# Graphic_LCD_Backpack.net
KiCad netlist of a schematic drawn in EAGLE
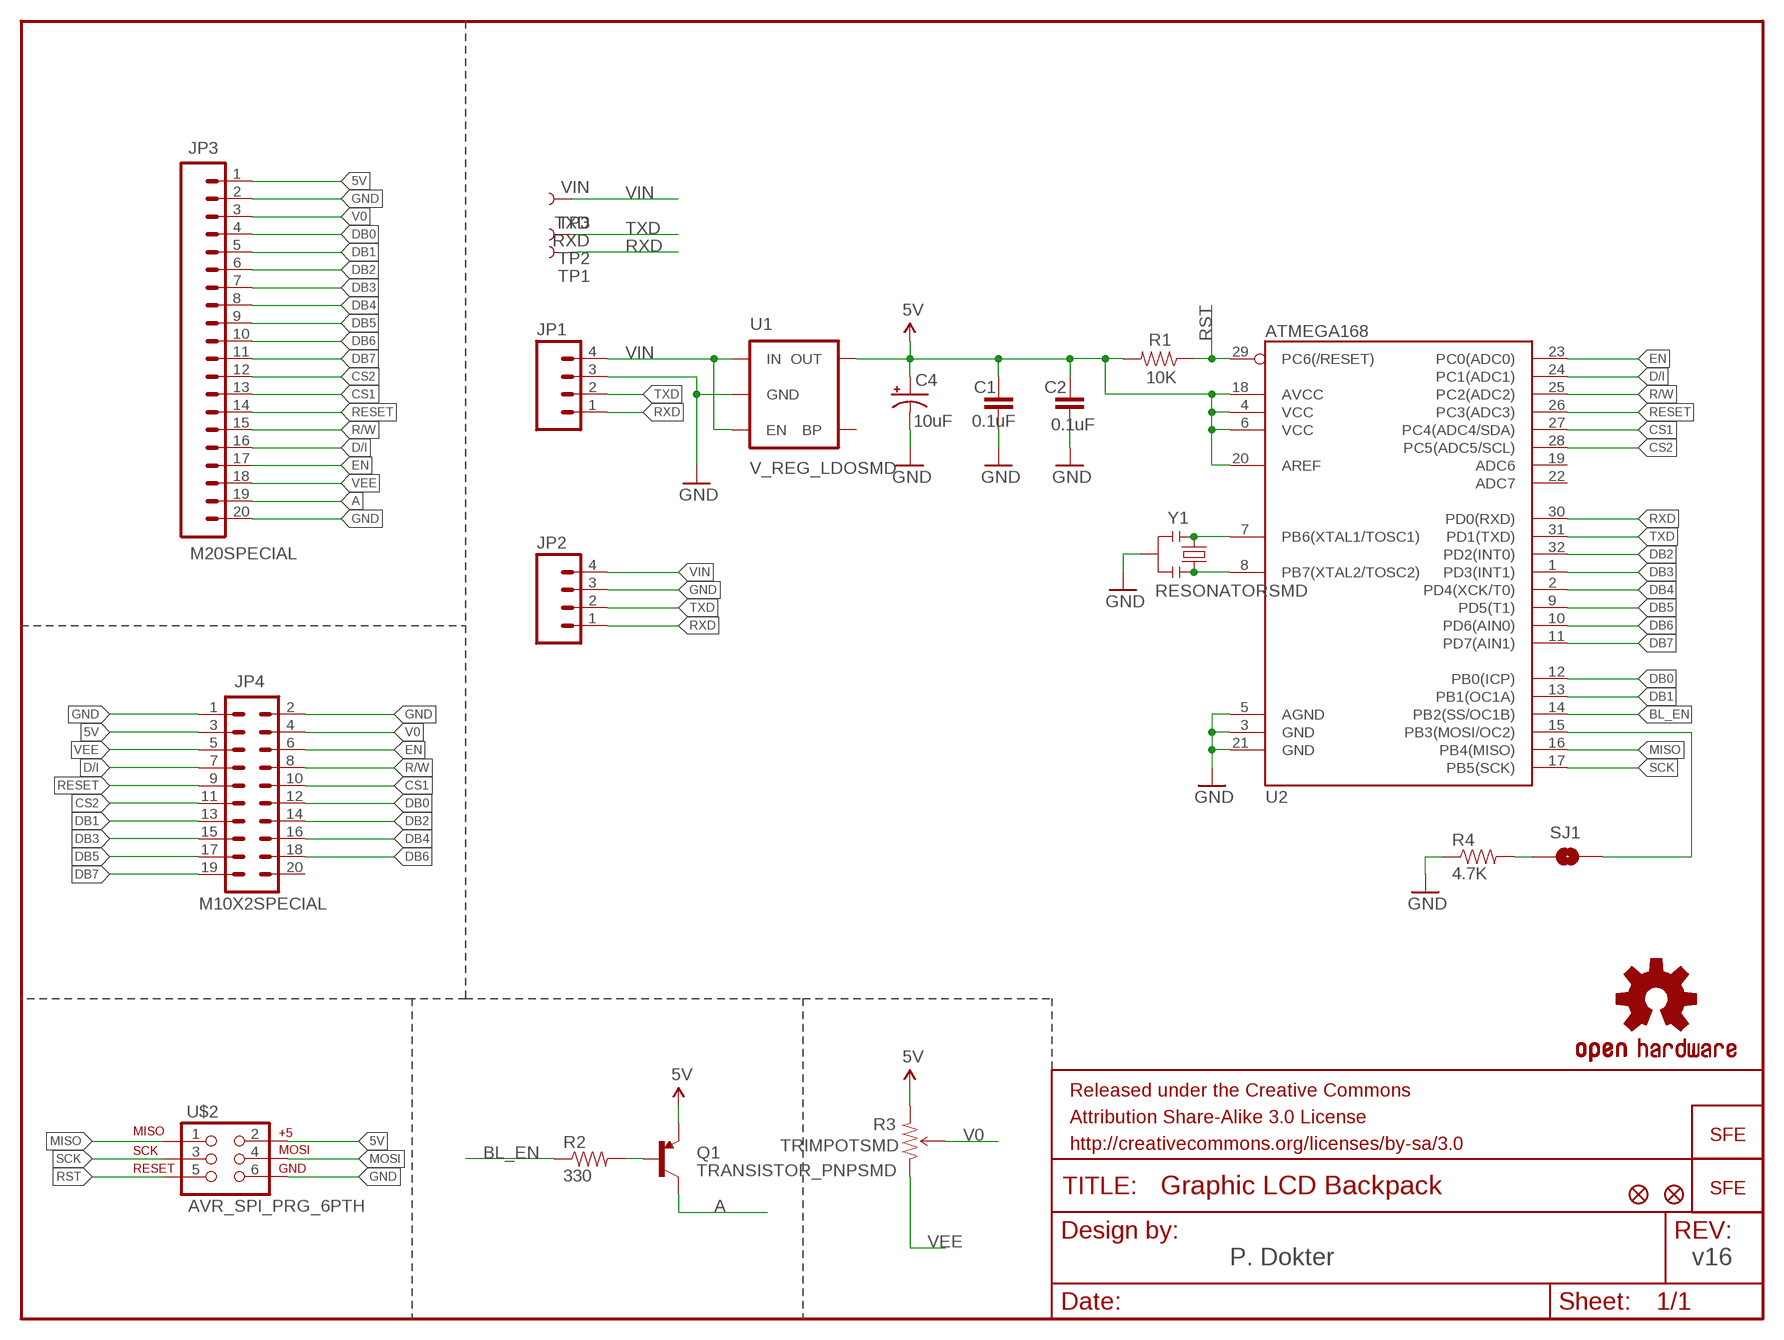
[diagram p0: schematic, sheet 1]

(export (version "E")
  (design (tool "Eeschema 10.0.6"))
  (components
    (comp (ref "C1")
      (value "0.1uF")
      (footprint "eagle-import:0603-CAP")
      (libsource (lib "eagle-import") (part "CAP0603-CAP"))
    )
    (comp (ref "C2")
      (value "0.1uF")
      (footprint "eagle-import:0603-CAP")
      (libsource (lib "eagle-import") (part "CAP0603-CAP"))
    )
    (comp (ref "C4")
      (value "10uF")
      (footprint "eagle-import:EIA3216")
      (libsource (lib "eagle-import") (part "CAP_POL1206"))
    )
    (comp (ref "FRAME1")
      (value "FRAME-LETTER")
      (footprint "eagle-import:CREATIVE_COMMONS")
      (libsource (lib "eagle-import") (part "FRAME-LETTER"))
    )
    (comp (ref "JP1")
      (value "M04SMD")
      (footprint "eagle-import:1X04-SMD")
      (libsource (lib "eagle-import") (part "M04SMD"))
    )
    (comp (ref "JP2")
      (value "M04PTH")
      (footprint "eagle-import:1X04")
      (libsource (lib "eagle-import") (part "M04PTH"))
    )
    (comp (ref "JP3")
      (value "M20SPECIAL")
      (footprint "eagle-import:1X20_LOCK_SPECIAL")
      (libsource (lib "eagle-import") (part "M20SPECIAL"))
    )
    (comp (ref "JP4")
      (value "M10X2SPECIAL")
      (footprint "eagle-import:2X10_LOCK_SPECIAL")
      (libsource (lib "eagle-import") (part "M10X2SPECIAL"))
    )
    (comp (ref "LOGO1")
      (value "OSHW-LOGOL")
      (footprint "eagle-import:OSHW-LOGO-L")
      (libsource (lib "eagle-import") (part "OSHW-LOGOL"))
    )
    (comp (ref "LOGO2")
      (value "LOGO-SFENEW")
      (footprint "eagle-import:SFE-NEW-WEBLOGO")
      (libsource (lib "eagle-import") (part "SparkFun-Aesthetics_LOGO-SFENEW"))
    )
    (comp (ref "LOGO3")
      (value "OSHW-LOGOS")
      (footprint "eagle-import:OSHW-LOGO-S")
      (libsource (lib "eagle-import") (part "OSHW-LOGOS"))
    )
    (comp (ref "Q1")
      (value "TRANSISTOR_PNPSMD")
      (footprint "eagle-import:SOT23-3")
      (libsource (lib "eagle-import") (part "TRANSISTOR_PNPSMD"))
    )
    (comp (ref "R1")
      (value "10K")
      (footprint "eagle-import:0603-RES")
      (libsource (lib "eagle-import") (part "RESISTOR0603-RES"))
    )
    (comp (ref "R2")
      (value "330")
      (footprint "eagle-import:0603-RES")
      (libsource (lib "eagle-import") (part "RESISTOR0603-RES"))
    )
    (comp (ref "R3")
      (value "TRIMPOTSMD")
      (footprint "eagle-import:TRIMPOT-3MM")
      (libsource (lib "eagle-import") (part "TRIMPOTSMD"))
    )
    (comp (ref "R4")
      (value "4.7K")
      (footprint "eagle-import:0603-RES")
      (libsource (lib "eagle-import") (part "RESISTOR0603-RES"))
    )
    (comp (ref "SJ1")
      (value "SOLDERJUMPERNC2")
      (footprint "eagle-import:SJ_2S-NOTRACE")
      (libsource (lib "eagle-import") (part "SOLDERJUMPERNC2"))
    )
    (comp (ref "TP1")
      (value "RXD")
      (footprint "eagle-import:PAD.03X.05")
      (libsource (lib "eagle-import") (part "TEST-POINT3X5"))
    )
    (comp (ref "TP2")
      (value "TXD")
      (footprint "eagle-import:PAD.03X.05")
      (libsource (lib "eagle-import") (part "TEST-POINT3X5"))
    )
    (comp (ref "TP3")
      (value "VIN")
      (footprint "eagle-import:PAD.03X.05")
      (libsource (lib "eagle-import") (part "TEST-POINT3X5"))
    )
    (comp (ref "U$2")
      (value "AVR_SPI_PRG_6PTH")
      (footprint "eagle-import:2X3")
      (libsource (lib "eagle-import") (part "AVR_SPI_PRG_6PTH"))
    )
    (comp (ref "U$8")
      (value "LOGO-SFENEW")
      (footprint "eagle-import:SFE-NEW-WEBLOGO")
      (libsource (lib "eagle-import") (part "LOGO-SFENEW"))
    )
    (comp (ref "U$9")
      (value "FIDUCIAL1X2")
      (footprint "eagle-import:FIDUCIAL-1X2")
      (libsource (lib "eagle-import") (part "FIDUCIAL1X2"))
    )
    (comp (ref "U$10")
      (value "FIDUCIAL1X2")
      (footprint "eagle-import:FIDUCIAL-1X2")
      (libsource (lib "eagle-import") (part "FIDUCIAL1X2"))
    )
    (comp (ref "U1")
      (value "V_REG_LDOSMD")
      (footprint "eagle-import:SOT23-5")
      (libsource (lib "eagle-import") (part "V_REG_LDOSMD"))
    )
    (comp (ref "U2")
      (value "ATMEGA168")
      (footprint "eagle-import:TQFP32-08")
      (libsource (lib "eagle-import") (part "ATMEGA168"))
    )
    (comp (ref "Y1")
      (value "RESONATORSMD")
      (footprint "eagle-import:RESONATOR-SMD")
      (libsource (lib "eagle-import") (part "RESONATORSMD"))
    )
  )
  (nets
    (net (code "1") (name "5V") (class "Default")
      (node (ref "C1") (pin "1") (pinfunction "1_1") (pintype "passive"))
      (node (ref "C2") (pin "2") (pinfunction "2_2") (pintype "passive"))
      (node (ref "C4") (pin "A") (pinfunction "+_A") (pintype "passive"))
      (node (ref "JP3") (pin "1") (pinfunction "1_1") (pintype "passive"))
      (node (ref "JP4") (pin "3") (pinfunction "3_3") (pintype "passive"))
      (node (ref "Q1") (pin "2") (pinfunction "E_2") (pintype "passive"))
      (node (ref "R1") (pin "2") (pinfunction "2_2") (pintype "passive"))
      (node (ref "R3") (pin "3") (pinfunction "CW_3") (pintype "passive"))
      (node (ref "U$2") (pin "2") (pinfunction "2_2") (pintype "passive"))
      (node (ref "U1") (pin "5") (pinfunction "OUT_5") (pintype "passive"))
      (node (ref "U2") (pin "18") (pinfunction "AVCC_18") (pintype "bidirectional"))
      (node (ref "U2") (pin "20") (pinfunction "AREF_20") (pintype "bidirectional"))
      (node (ref "U2") (pin "4") (pinfunction "VCC_4") (pintype "bidirectional"))
      (node (ref "U2") (pin "6") (pinfunction "VCC_6") (pintype "bidirectional"))
    )
    (net (code "2") (name "A") (class "Default")
      (node (ref "JP3") (pin "19") (pinfunction "19_19") (pintype "passive"))
      (node (ref "Q1") (pin "3") (pinfunction "C_3") (pintype "passive"))
    )
    (net (code "3") (name "BL_EN") (class "Default")
      (node (ref "R2") (pin "1") (pinfunction "1_1") (pintype "passive"))
      (node (ref "U2") (pin "14") (pinfunction "PB2(SS/OC1B)_14") (pintype "bidirectional"))
    )
    (net (code "4") (name "CS1") (class "Default")
      (node (ref "JP3") (pin "13") (pinfunction "13_13") (pintype "passive"))
      (node (ref "JP4") (pin "10") (pinfunction "10_10") (pintype "passive"))
      (node (ref "U2") (pin "27") (pinfunction "PC4(ADC4/SDA)_27") (pintype "bidirectional"))
    )
    (net (code "5") (name "CS2") (class "Default")
      (node (ref "JP3") (pin "12") (pinfunction "12_12") (pintype "passive"))
      (node (ref "JP4") (pin "11") (pinfunction "11_11") (pintype "passive"))
      (node (ref "U2") (pin "28") (pinfunction "PC5(ADC5/SCL)_28") (pintype "bidirectional"))
    )
    (net (code "6") (name "DB0") (class "Default")
      (node (ref "JP3") (pin "4") (pinfunction "4_4") (pintype "passive"))
      (node (ref "JP4") (pin "12") (pinfunction "12_12") (pintype "passive"))
      (node (ref "U2") (pin "12") (pinfunction "PB0(ICP)_12") (pintype "bidirectional"))
    )
    (net (code "7") (name "DB1") (class "Default")
      (node (ref "JP3") (pin "5") (pinfunction "5_5") (pintype "passive"))
      (node (ref "JP4") (pin "13") (pinfunction "13_13") (pintype "passive"))
      (node (ref "U2") (pin "13") (pinfunction "PB1(OC1A)_13") (pintype "bidirectional"))
    )
    (net (code "8") (name "DB2") (class "Default")
      (node (ref "JP3") (pin "6") (pinfunction "6_6") (pintype "passive"))
      (node (ref "JP4") (pin "14") (pinfunction "14_14") (pintype "passive"))
      (node (ref "U2") (pin "32") (pinfunction "PD2(INT0)_32") (pintype "bidirectional"))
    )
    (net (code "9") (name "DB3") (class "Default")
      (node (ref "JP3") (pin "7") (pinfunction "7_7") (pintype "passive"))
      (node (ref "JP4") (pin "15") (pinfunction "15_15") (pintype "passive"))
      (node (ref "U2") (pin "1") (pinfunction "PD3(INT1)_1") (pintype "bidirectional"))
    )
    (net (code "10") (name "DB4") (class "Default")
      (node (ref "JP3") (pin "8") (pinfunction "8_8") (pintype "passive"))
      (node (ref "JP4") (pin "16") (pinfunction "16_16") (pintype "passive"))
      (node (ref "U2") (pin "2") (pinfunction "PD4(XCK/T0)_2") (pintype "bidirectional"))
    )
    (net (code "11") (name "DB5") (class "Default")
      (node (ref "JP3") (pin "9") (pinfunction "9_9") (pintype "passive"))
      (node (ref "JP4") (pin "17") (pinfunction "17_17") (pintype "passive"))
      (node (ref "U2") (pin "9") (pinfunction "PD5(T1)_9") (pintype "bidirectional"))
    )
    (net (code "12") (name "DB6") (class "Default")
      (node (ref "JP3") (pin "10") (pinfunction "10_10") (pintype "passive"))
      (node (ref "JP4") (pin "18") (pinfunction "18_18") (pintype "passive"))
      (node (ref "U2") (pin "10") (pinfunction "PD6(AIN0)_10") (pintype "bidirectional"))
    )
    (net (code "13") (name "DB7") (class "Default")
      (node (ref "JP3") (pin "11") (pinfunction "11_11") (pintype "passive"))
      (node (ref "JP4") (pin "19") (pinfunction "19_19") (pintype "passive"))
      (node (ref "U2") (pin "11") (pinfunction "PD7(AIN1)_11") (pintype "bidirectional"))
    )
    (net (code "14") (name "D{slash}I") (class "Default")
      (node (ref "JP3") (pin "16") (pinfunction "16_16") (pintype "passive"))
      (node (ref "JP4") (pin "7") (pinfunction "7_7") (pintype "passive"))
      (node (ref "U2") (pin "24") (pinfunction "PC1(ADC1)_24") (pintype "bidirectional"))
    )
    (net (code "15") (name "EN") (class "Default")
      (node (ref "JP3") (pin "17") (pinfunction "17_17") (pintype "passive"))
      (node (ref "JP4") (pin "6") (pinfunction "6_6") (pintype "passive"))
      (node (ref "U2") (pin "23") (pinfunction "PC0(ADC0)_23") (pintype "bidirectional"))
    )
    (net (code "16") (name "GND") (class "Default")
      (node (ref "C1") (pin "2") (pinfunction "2_2") (pintype "passive"))
      (node (ref "C2") (pin "1") (pinfunction "1_1") (pintype "passive"))
      (node (ref "C4") (pin "C") (pinfunction "-_C") (pintype "passive"))
      (node (ref "JP1") (pin "3") (pinfunction "3_3") (pintype "passive"))
      (node (ref "JP2") (pin "3") (pinfunction "3_3") (pintype "passive"))
      (node (ref "JP3") (pin "2") (pinfunction "2_2") (pintype "passive"))
      (node (ref "JP3") (pin "20") (pinfunction "20_20") (pintype "passive"))
      (node (ref "JP4") (pin "1") (pinfunction "1_1") (pintype "passive"))
      (node (ref "JP4") (pin "2") (pinfunction "2_2") (pintype "passive"))
      (node (ref "R4") (pin "1") (pinfunction "1_1") (pintype "passive"))
      (node (ref "U$2") (pin "6") (pinfunction "6_6") (pintype "passive"))
      (node (ref "U1") (pin "2") (pinfunction "GND_2") (pintype "input"))
      (node (ref "U2") (pin "21") (pinfunction "GND_21") (pintype "bidirectional"))
      (node (ref "U2") (pin "3") (pinfunction "GND_3") (pintype "bidirectional"))
      (node (ref "U2") (pin "5") (pinfunction "AGND_5") (pintype "bidirectional"))
      (node (ref "Y1") (pin "2") (pinfunction "2_2") (pintype "passive"))
    )
    (net (code "17") (name "MISO") (class "Default")
      (node (ref "U$2") (pin "1") (pinfunction "1_1") (pintype "passive"))
      (node (ref "U2") (pin "16") (pinfunction "PB4(MISO)_16") (pintype "bidirectional"))
    )
    (net (code "18") (name "MOSI") (class "Default")
      (node (ref "SJ1") (pin "2") (pinfunction "2_2") (pintype "passive"))
      (node (ref "U$2") (pin "4") (pinfunction "4_4") (pintype "passive"))
      (node (ref "U2") (pin "15") (pinfunction "PB3(MOSI/OC2)_15") (pintype "bidirectional"))
    )
    (net (code "19") (name "Net-(Q1-B)") (class "Default")
      (node (ref "Q1") (pin "1") (pinfunction "B_1") (pintype "passive"))
      (node (ref "R2") (pin "2") (pinfunction "2_2") (pintype "passive"))
    )
    (net (code "20") (name "Net-(R4-Pad2)") (class "Default")
      (node (ref "R4") (pin "2") (pinfunction "2_2") (pintype "passive"))
      (node (ref "SJ1") (pin "1") (pinfunction "1_1") (pintype "passive"))
    )
    (net (code "21") (name "Net-(U2-PB6(XTAL1{slash}TOSC1))") (class "Default")
      (node (ref "U2") (pin "7") (pinfunction "PB6(XTAL1/TOSC1)_7") (pintype "bidirectional"))
      (node (ref "Y1") (pin "1") (pinfunction "1_1") (pintype "passive"))
    )
    (net (code "22") (name "Net-(U2-PB7(XTAL2{slash}TOSC2))") (class "Default")
      (node (ref "U2") (pin "8") (pinfunction "PB7(XTAL2/TOSC2)_8") (pintype "bidirectional"))
      (node (ref "Y1") (pin "3") (pinfunction "3_3") (pintype "passive"))
    )
    (net (code "23") (name "RESET") (class "Default")
      (node (ref "JP3") (pin "14") (pinfunction "14_14") (pintype "passive"))
      (node (ref "JP4") (pin "9") (pinfunction "9_9") (pintype "passive"))
      (node (ref "U2") (pin "26") (pinfunction "PC3(ADC3)_26") (pintype "bidirectional"))
    )
    (net (code "24") (name "RST") (class "Default")
      (node (ref "R1") (pin "1") (pinfunction "1_1") (pintype "passive"))
      (node (ref "U$2") (pin "5") (pinfunction "5_5") (pintype "passive"))
      (node (ref "U2") (pin "29") (pinfunction "PC6(/RESET)_29") (pintype "bidirectional"))
    )
    (net (code "25") (name "RXD") (class "Default")
      (node (ref "JP1") (pin "1") (pinfunction "1_1") (pintype "passive"))
      (node (ref "JP2") (pin "1") (pinfunction "1_1") (pintype "passive"))
      (node (ref "TP1") (pin "P$1") (pinfunction "1_P$1") (pintype "bidirectional"))
      (node (ref "U2") (pin "30") (pinfunction "PD0(RXD)_30") (pintype "bidirectional"))
    )
    (net (code "26") (name "R{slash}W") (class "Default")
      (node (ref "JP3") (pin "15") (pinfunction "15_15") (pintype "passive"))
      (node (ref "JP4") (pin "8") (pinfunction "8_8") (pintype "passive"))
      (node (ref "U2") (pin "25") (pinfunction "PC2(ADC2)_25") (pintype "bidirectional"))
    )
    (net (code "27") (name "SCK") (class "Default")
      (node (ref "U$2") (pin "3") (pinfunction "3_3") (pintype "passive"))
      (node (ref "U2") (pin "17") (pinfunction "PB5(SCK)_17") (pintype "bidirectional"))
    )
    (net (code "28") (name "TXD") (class "Default")
      (node (ref "JP1") (pin "2") (pinfunction "2_2") (pintype "passive"))
      (node (ref "JP2") (pin "2") (pinfunction "2_2") (pintype "passive"))
      (node (ref "TP2") (pin "P$1") (pinfunction "1_P$1") (pintype "bidirectional"))
      (node (ref "U2") (pin "31") (pinfunction "PD1(TXD)_31") (pintype "bidirectional"))
    )
    (net (code "29") (name "V0") (class "Default")
      (node (ref "JP3") (pin "3") (pinfunction "3_3") (pintype "passive"))
      (node (ref "JP4") (pin "4") (pinfunction "4_4") (pintype "passive"))
      (node (ref "R3") (pin "2") (pinfunction "WIPER_2") (pintype "passive"))
    )
    (net (code "30") (name "VEE") (class "Default")
      (node (ref "JP3") (pin "18") (pinfunction "18_18") (pintype "passive"))
      (node (ref "JP4") (pin "5") (pinfunction "5_5") (pintype "passive"))
      (node (ref "R3") (pin "1") (pinfunction "CCW_1") (pintype "passive"))
    )
    (net (code "31") (name "VIN") (class "Default")
      (node (ref "JP1") (pin "4") (pinfunction "4_4") (pintype "passive"))
      (node (ref "JP2") (pin "4") (pinfunction "4_4") (pintype "passive"))
      (node (ref "TP3") (pin "P$1") (pinfunction "1_P$1") (pintype "bidirectional"))
      (node (ref "U1") (pin "1") (pinfunction "IN_1") (pintype "input"))
      (node (ref "U1") (pin "3") (pinfunction "EN_3") (pintype "input"))
    )
    (net (code "32") (name "unconnected-(JP4-Pad20)") (class "Default")
      (node (ref "JP4") (pin "20") (pinfunction "20_20") (pintype "passive"))
    )
    (net (code "33") (name "unconnected-(U1-BP-Pad4)") (class "Default")
      (node (ref "U1") (pin "4") (pinfunction "BP_4") (pintype "input"))
    )
    (net (code "34") (name "unconnected-(U2-ADC6-Pad19)") (class "Default")
      (node (ref "U2") (pin "19") (pinfunction "ADC6_19") (pintype "bidirectional"))
    )
    (net (code "35") (name "unconnected-(U2-ADC7-Pad22)") (class "Default")
      (node (ref "U2") (pin "22") (pinfunction "ADC7_22") (pintype "bidirectional"))
    )
  )
)
